# CON_NANOTALK_10WHDRRAMx2.net
KiCad netlist of a schematic drawn in Altium Designer
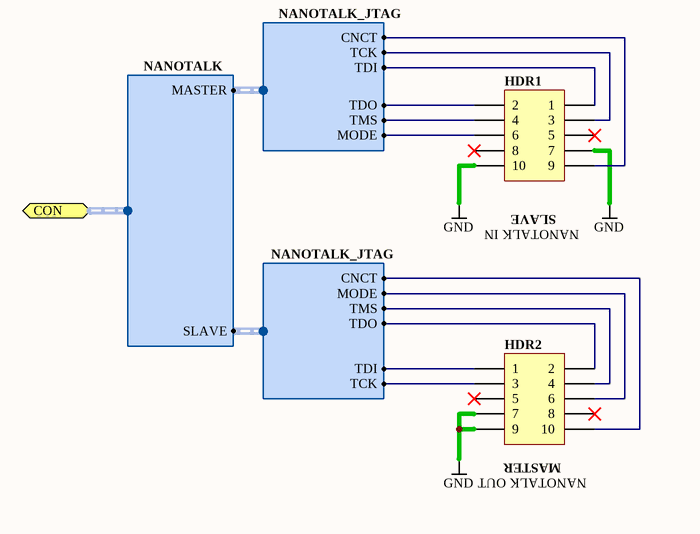
[diagram p0: CON_NANOTALK_10WHDRRAMx2.SchDoc]

(export (version "E")
  (design (tool "Eeschema 10.0.6"))
  (components
    (comp (ref "HDR1")
      (value "2x5 RA HEADER MALE")
      (footprint "918510x323")
      (description "Header IDC, 2 x 5 Pin Right-Angle 2.54mm Pitch (Non-Boxed, Male)")
      (libsource (lib "altium-import") (part "root_0_mirrored_CON-HDR-2x5-RA_"))
    )
    (comp (ref "HDR2")
      (value "2x5 RA HEADER")
      (footprint "918510x323")
      (description "Header IDC, 2 x 5 Pin Right-Angle 2.54mm Pitch (Non-Boxed, Male)")
      (libsource (lib "altium-import") (part "root_0_CON-HDR-2x5-RA_"))
    )
  )
  (nets
    (net (code "7") (name "GND") (class "Default")
      (node (ref "HDR1") (pin "10") (pinfunction "10_10") (pintype "passive"))
      (node (ref "HDR1") (pin "7") (pinfunction "7_7") (pintype "passive"))
      (node (ref "HDR2") (pin "7") (pinfunction "7_7") (pintype "passive"))
      (node (ref "HDR2") (pin "9") (pinfunction "9_9") (pintype "passive"))
    )
    (net (code "8") (name "unconnected-(HDR1-Pad1)") (class "Default")
      (node (ref "HDR1") (pin "1") (pinfunction "1_1") (pintype "passive"))
    )
    (net (code "9") (name "unconnected-(HDR1-Pad2)") (class "Default")
      (node (ref "HDR1") (pin "2") (pinfunction "2_2") (pintype "passive"))
    )
    (net (code "10") (name "unconnected-(HDR1-Pad3)") (class "Default")
      (node (ref "HDR1") (pin "3") (pinfunction "3_3") (pintype "passive"))
    )
    (net (code "11") (name "unconnected-(HDR1-Pad4)") (class "Default")
      (node (ref "HDR1") (pin "4") (pinfunction "4_4") (pintype "passive"))
    )
    (net (code "12") (name "unconnected-(HDR1-Pad5)") (class "Default")
      (node (ref "HDR1") (pin "5") (pinfunction "5_5") (pintype "passive+no_connect"))
    )
    (net (code "13") (name "unconnected-(HDR1-Pad6)") (class "Default")
      (node (ref "HDR1") (pin "6") (pinfunction "6_6") (pintype "passive"))
    )
    (net (code "14") (name "unconnected-(HDR1-Pad8)") (class "Default")
      (node (ref "HDR1") (pin "8") (pinfunction "8_8") (pintype "passive+no_connect"))
    )
    (net (code "15") (name "unconnected-(HDR1-Pad9)") (class "Default")
      (node (ref "HDR1") (pin "9") (pinfunction "9_9") (pintype "passive"))
    )
    (net (code "16") (name "unconnected-(HDR2-Pad1)") (class "Default")
      (node (ref "HDR2") (pin "1") (pinfunction "1_1") (pintype "passive"))
    )
    (net (code "17") (name "unconnected-(HDR2-Pad2)") (class "Default")
      (node (ref "HDR2") (pin "2") (pinfunction "2_2") (pintype "passive"))
    )
    (net (code "18") (name "unconnected-(HDR2-Pad3)") (class "Default")
      (node (ref "HDR2") (pin "3") (pinfunction "3_3") (pintype "passive"))
    )
    (net (code "19") (name "unconnected-(HDR2-Pad4)") (class "Default")
      (node (ref "HDR2") (pin "4") (pinfunction "4_4") (pintype "passive"))
    )
    (net (code "20") (name "unconnected-(HDR2-Pad5)") (class "Default")
      (node (ref "HDR2") (pin "5") (pinfunction "5_5") (pintype "passive+no_connect"))
    )
    (net (code "21") (name "unconnected-(HDR2-Pad6)") (class "Default")
      (node (ref "HDR2") (pin "6") (pinfunction "6_6") (pintype "passive"))
    )
    (net (code "22") (name "unconnected-(HDR2-Pad8)") (class "Default")
      (node (ref "HDR2") (pin "8") (pinfunction "8_8") (pintype "passive+no_connect"))
    )
    (net (code "23") (name "unconnected-(HDR2-Pad10)") (class "Default")
      (node (ref "HDR2") (pin "10") (pinfunction "10_10") (pintype "passive"))
    )
  )
)
